# MCU.net
KiCad netlist of a schematic drawn in Altium Designer
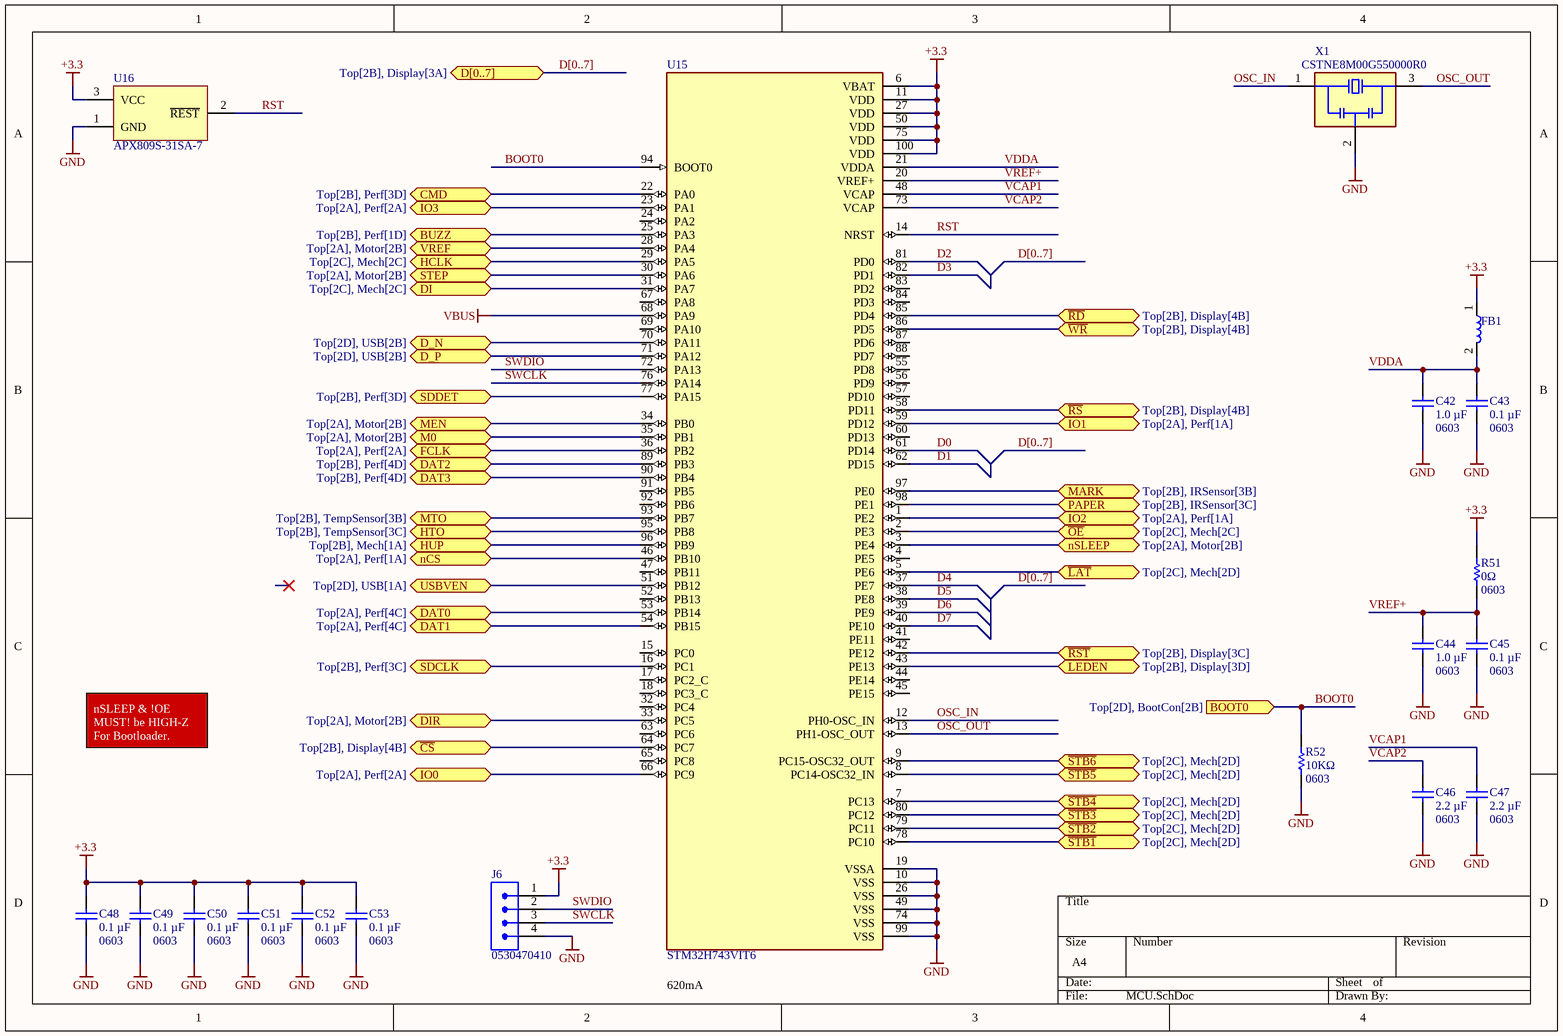
[diagram p0: MCU.SchDoc]

(export (version "E")
  (design (tool "Eeschema 10.0.6"))
  (components
    (comp (ref "C42")
      (value "1.0 µF")
      (footprint "0603")
      (description "1 µF ±10% 50V Ceramic Capacitor X7T 0603 (1608 Metric)")
      (fields (field (name "CASE") "0603") (field (name "TOLERANCE") "±10%") (field (name "VOLTAGE") "50V"))
      (libsource (lib "Murata Electronics") (part "GRM188D71H105KE01J"))
    )
    (comp (ref "C43")
      (value "0.1 µF")
      (footprint "0603")
      (description "0.1 µF ±20% 100V Ceramic Capacitor X7R 0603 (1608 Metric)")
      (fields (field (name "CASE") "0603") (field (name "TOLERANCE") "±20%") (field (name "VOLTAGE") "100V"))
      (libsource (lib "Murata Electronics") (part "GRM188R72A104MA35J"))
    )
    (comp (ref "C44")
      (value "1.0 µF")
      (footprint "0603")
      (description "1 µF ±10% 50V Ceramic Capacitor X7T 0603 (1608 Metric)")
      (fields (field (name "CASE") "0603") (field (name "TOLERANCE") "±10%") (field (name "VOLTAGE") "50V"))
      (libsource (lib "Murata Electronics") (part "GRM188D71H105KE01J"))
    )
    (comp (ref "C45")
      (value "0.1 µF")
      (footprint "0603")
      (description "0.1 µF ±20% 100V Ceramic Capacitor X7R 0603 (1608 Metric)")
      (fields (field (name "CASE") "0603") (field (name "TOLERANCE") "±20%") (field (name "VOLTAGE") "100V"))
      (libsource (lib "Murata Electronics") (part "GRM188R72A104MA35J"))
    )
    (comp (ref "C46")
      (value "2.2 µF")
      (footprint "0603")
      (description "2.2 µF ±10% 25V Ceramic Capacitor X5R 0603 (1608 Metric)")
      (fields (field (name "CASE") "0603") (field (name "TOLERANCE") "±10%") (field (name "VOLTAGE") "25V"))
      (libsource (lib "Murata Electronics") (part "GRM188R61E225KA12J"))
    )
    (comp (ref "C47")
      (value "2.2 µF")
      (footprint "0603")
      (description "2.2 µF ±10% 25V Ceramic Capacitor X5R 0603 (1608 Metric)")
      (fields (field (name "CASE") "0603") (field (name "TOLERANCE") "±10%") (field (name "VOLTAGE") "25V"))
      (libsource (lib "Murata Electronics") (part "GRM188R61E225KA12J"))
    )
    (comp (ref "C48")
      (value "0.1 µF")
      (footprint "0603")
      (description "0.1 µF ±20% 100V Ceramic Capacitor X7R 0603 (1608 Metric)")
      (fields (field (name "CASE") "0603") (field (name "TOLERANCE") "±20%") (field (name "VOLTAGE") "100V"))
      (libsource (lib "Murata Electronics") (part "GRM188R72A104MA35J"))
    )
    (comp (ref "C49")
      (value "0.1 µF")
      (footprint "0603")
      (description "0.1 µF ±20% 100V Ceramic Capacitor X7R 0603 (1608 Metric)")
      (fields (field (name "CASE") "0603") (field (name "TOLERANCE") "±20%") (field (name "VOLTAGE") "100V"))
      (libsource (lib "Murata Electronics") (part "GRM188R72A104MA35J"))
    )
    (comp (ref "C50")
      (value "0.1 µF")
      (footprint "0603")
      (description "0.1 µF ±20% 100V Ceramic Capacitor X7R 0603 (1608 Metric)")
      (fields (field (name "CASE") "0603") (field (name "TOLERANCE") "±20%") (field (name "VOLTAGE") "100V"))
      (libsource (lib "Murata Electronics") (part "GRM188R72A104MA35J"))
    )
    (comp (ref "C51")
      (value "0.1 µF")
      (footprint "0603")
      (description "0.1 µF ±20% 100V Ceramic Capacitor X7R 0603 (1608 Metric)")
      (fields (field (name "CASE") "0603") (field (name "TOLERANCE") "±20%") (field (name "VOLTAGE") "100V"))
      (libsource (lib "Murata Electronics") (part "GRM188R72A104MA35J"))
    )
    (comp (ref "C52")
      (value "0.1 µF")
      (footprint "0603")
      (description "0.1 µF ±20% 100V Ceramic Capacitor X7R 0603 (1608 Metric)")
      (fields (field (name "CASE") "0603") (field (name "TOLERANCE") "±20%") (field (name "VOLTAGE") "100V"))
      (libsource (lib "Murata Electronics") (part "GRM188R72A104MA35J"))
    )
    (comp (ref "C53")
      (value "0.1 µF")
      (footprint "0603")
      (description "0.1 µF ±20% 100V Ceramic Capacitor X7R 0603 (1608 Metric)")
      (fields (field (name "CASE") "0603") (field (name "TOLERANCE") "±20%") (field (name "VOLTAGE") "100V"))
      (libsource (lib "Murata Electronics") (part "GRM188R72A104MA35J"))
    )
    (comp (ref "FB1")
      (value "MPZ1608S221ATA00")
      (footprint "0603")
      (description "220 Ohms @ 100 MHz 1 Power Line Ferrite Bead 0603 (1608 Metric) 2.2A 50mOhm")
      (libsource (lib "TDK Corporation") (part "MPZ1608S221ATA00"))
    )
    (comp (ref "J6")
      (value "0530470410")
      (footprint "4POS")
      (description "Connector Header Through Hole 4 position 0.049\" (1.25mm)")
      (libsource (lib "Molex") (part "0530470410"))
    )
    (comp (ref "R51")
      (value "0Ω")
      (footprint "0603")
      (description "0 Ohms Jumper Chip Resistor 0603 (1608 Metric) Automotive AEC-Q200 Thick Film")
      (fields
        (field (name "CASE") "0603")
        (field (name "TOLERANCE") "0")
        (field (name "Comment") "RMCF0603ZT0R00")
      )
      (libsource (lib "Stackpole Electronics Inc") (part "RMCF0603ZT0R00"))
    )
    (comp (ref "R52")
      (value "10KΩ")
      (footprint "0603")
      (description "10 kOhms ±1% 0.1W, 1/10W Chip Resistor 0603 (1608 Metric) Automotive AEC-Q200 Thick Film")
      (fields (field (name "CASE") "0603") (field (name "TOLERANCE") "1%") (field (name "POWER") "0.1W"))
      (libsource (lib "Stackpole Electronics Inc") (part "RMCF0603FG10K0"))
    )
    (comp (ref "U15")
      (value "STM32H743VIT6")
      (footprint "100-LQFP")
      (libsource (lib "STMicroelectronics") (part "STM32H743VIT6"))
    )
    (comp (ref "U16")
      (value "APX809S-31SA-7")
      (footprint "SOT-23-3")
      (description "Supervisor Push-Pull, Totem Pole 1 Channel SOT-23-3")
      (libsource (lib "Diodes Incorporated") (part "APX809S-31SA-7"))
    )
    (comp (ref "X1")
      (value "CSTNE8M00G550000R0")
      (footprint "3-SMD")
      (description "8 MHz Ceramic Resonator Built in Capacitor 33 pF ±0.2% 40 Ohms -40°C ~ 85°C Surface Mount")
      (libsource (lib "Murata Electronics") (part "CSTNE8M00G550000R0"))
    )
  )
  (nets
    (net (code "1") (name "+3.3") (class "Default")
      (node (ref "C48") (pin "2") (pinfunction "2_2") (pintype "passive"))
      (node (ref "C49") (pin "2") (pinfunction "2_2") (pintype "passive"))
      (node (ref "C50") (pin "2") (pinfunction "2_2") (pintype "passive"))
      (node (ref "C51") (pin "2") (pinfunction "2_2") (pintype "passive"))
      (node (ref "C52") (pin "2") (pinfunction "2_2") (pintype "passive"))
      (node (ref "C53") (pin "2") (pinfunction "2_2") (pintype "passive"))
      (node (ref "FB1") (pin "1") (pinfunction "1_1") (pintype "passive"))
      (node (ref "J6") (pin "1") (pinfunction "1_1") (pintype "passive"))
      (node (ref "R51") (pin "1") (pinfunction "1_1") (pintype "passive"))
      (node (ref "U15") (pin "100") (pinfunction "VDD_100") (pintype "power_in"))
      (node (ref "U15") (pin "11") (pinfunction "VDD_11") (pintype "power_in"))
      (node (ref "U15") (pin "27") (pinfunction "VDD_27") (pintype "power_in"))
      (node (ref "U15") (pin "50") (pinfunction "VDD_50") (pintype "power_in"))
      (node (ref "U15") (pin "6") (pinfunction "VBAT_6") (pintype "power_in"))
      (node (ref "U15") (pin "75") (pinfunction "VDD_75") (pintype "power_in"))
      (node (ref "U16") (pin "3") (pinfunction "VCC_3") (pintype "passive"))
    )
    (net (code "2") (name "/BOOT0") (class "Default")
      (node (ref "R52") (pin "2") (pinfunction "2_2") (pintype "passive"))
      (node (ref "U15") (pin "94") (pinfunction "BOOT0_94") (pintype "input"))
    )
    (net (code "3") (name "/BUZZ") (class "Default")
      (node (ref "U15") (pin "25") (pinfunction "PA3_25") (pintype "bidirectional"))
    )
    (net (code "4") (name "/CMD") (class "Default")
      (node (ref "U15") (pin "22") (pinfunction "PA0_22") (pintype "bidirectional"))
    )
    (net (code "5") (name "/D0") (class "Default")
      (node (ref "U15") (pin "61") (pinfunction "PD14_61") (pintype "bidirectional"))
    )
    (net (code "6") (name "/D1") (class "Default")
      (node (ref "U15") (pin "62") (pinfunction "PD15_62") (pintype "bidirectional"))
    )
    (net (code "7") (name "/D2") (class "Default")
      (node (ref "U15") (pin "81") (pinfunction "PD0_81") (pintype "bidirectional"))
    )
    (net (code "8") (name "/D3") (class "Default")
      (node (ref "U15") (pin "82") (pinfunction "PD1_82") (pintype "bidirectional"))
    )
    (net (code "9") (name "/D4") (class "Default")
      (node (ref "U15") (pin "37") (pinfunction "PE7_37") (pintype "bidirectional"))
    )
    (net (code "10") (name "/D5") (class "Default")
      (node (ref "U15") (pin "38") (pinfunction "PE8_38") (pintype "bidirectional"))
    )
    (net (code "11") (name "/D6") (class "Default")
      (node (ref "U15") (pin "39") (pinfunction "PE9_39") (pintype "bidirectional"))
    )
    (net (code "12") (name "/D7") (class "Default")
      (node (ref "U15") (pin "40") (pinfunction "PE10_40") (pintype "bidirectional"))
    )
    (net (code "13") (name "/DAT0") (class "Default")
      (node (ref "U15") (pin "53") (pinfunction "PB14_53") (pintype "bidirectional"))
    )
    (net (code "14") (name "/DAT1") (class "Default")
      (node (ref "U15") (pin "54") (pinfunction "PB15_54") (pintype "bidirectional"))
    )
    (net (code "15") (name "/DAT2") (class "Default")
      (node (ref "U15") (pin "89") (pinfunction "PB3_89") (pintype "bidirectional"))
    )
    (net (code "16") (name "/DAT3") (class "Default")
      (node (ref "U15") (pin "90") (pinfunction "PB4_90") (pintype "bidirectional"))
    )
    (net (code "17") (name "/DI") (class "Default")
      (node (ref "U15") (pin "31") (pinfunction "PA7_31") (pintype "bidirectional"))
    )
    (net (code "18") (name "/DIR") (class "Default")
      (node (ref "U15") (pin "33") (pinfunction "PC5_33") (pintype "bidirectional"))
    )
    (net (code "20") (name "/D_N") (class "Default")
      (node (ref "U15") (pin "70") (pinfunction "PA11_70") (pintype "bidirectional"))
    )
    (net (code "21") (name "/D_P") (class "Default")
      (node (ref "U15") (pin "71") (pinfunction "PA12_71") (pintype "bidirectional"))
    )
    (net (code "22") (name "/FCLK") (class "Default")
      (node (ref "U15") (pin "36") (pinfunction "PB2_36") (pintype "bidirectional"))
    )
    (net (code "23") (name "/HCLK") (class "Default")
      (node (ref "U15") (pin "29") (pinfunction "PA5_29") (pintype "bidirectional"))
    )
    (net (code "24") (name "/HTO") (class "Default")
      (node (ref "U15") (pin "95") (pinfunction "PB8_95") (pintype "bidirectional"))
    )
    (net (code "25") (name "/HUP") (class "Default")
      (node (ref "U15") (pin "96") (pinfunction "PB9_96") (pintype "bidirectional"))
    )
    (net (code "26") (name "/IO0") (class "Default")
      (node (ref "U15") (pin "66") (pinfunction "PC9_66") (pintype "bidirectional"))
    )
    (net (code "27") (name "/IO1") (class "Default")
      (node (ref "U15") (pin "59") (pinfunction "PD12_59") (pintype "bidirectional"))
    )
    (net (code "28") (name "/IO2") (class "Default")
      (node (ref "U15") (pin "1") (pinfunction "PE2_1") (pintype "bidirectional"))
    )
    (net (code "29") (name "/IO3") (class "Default")
      (node (ref "U15") (pin "23") (pinfunction "PA1_23") (pintype "bidirectional"))
    )
    (net (code "30") (name "/LEDEN") (class "Default")
      (node (ref "U15") (pin "43") (pinfunction "PE13_43") (pintype "bidirectional"))
    )
    (net (code "31") (name "/M0") (class "Default")
      (node (ref "U15") (pin "35") (pinfunction "PB1_35") (pintype "bidirectional"))
    )
    (net (code "32") (name "/MARK") (class "Default")
      (node (ref "U15") (pin "97") (pinfunction "PE0_97") (pintype "bidirectional"))
    )
    (net (code "33") (name "/MEN") (class "Default")
      (node (ref "U15") (pin "34") (pinfunction "PB0_34") (pintype "bidirectional"))
    )
    (net (code "34") (name "/MTO") (class "Default")
      (node (ref "U15") (pin "93") (pinfunction "PB7_93") (pintype "bidirectional"))
    )
    (net (code "35") (name "/OSC_IN") (class "Default")
      (node (ref "U15") (pin "12") (pinfunction "PH0-OSC_IN_12") (pintype "bidirectional"))
      (node (ref "X1") (pin "1") (pinfunction "IN_1") (pintype "passive"))
    )
    (net (code "36") (name "/OSC_OUT") (class "Default")
      (node (ref "U15") (pin "13") (pinfunction "PH1-OSC_OUT_13") (pintype "bidirectional"))
      (node (ref "X1") (pin "3") (pinfunction "OUT_3") (pintype "passive"))
    )
    (net (code "37") (name "/PAPER") (class "Default")
      (node (ref "U15") (pin "98") (pinfunction "PE1_98") (pintype "bidirectional"))
    )
    (net (code "38") (name "/RST") (class "Default")
      (node (ref "U15") (pin "14") (pinfunction "NRST_14") (pintype "bidirectional"))
      (node (ref "U16") (pin "2") (pinfunction "~{REST}_2") (pintype "passive"))
    )
    (net (code "39") (name "/SDCLK") (class "Default")
      (node (ref "U15") (pin "16") (pinfunction "PC1_16") (pintype "bidirectional"))
    )
    (net (code "40") (name "/SDDET") (class "Default")
      (node (ref "U15") (pin "77") (pinfunction "PA15_77") (pintype "bidirectional"))
    )
    (net (code "41") (name "/STEP") (class "Default")
      (node (ref "U15") (pin "30") (pinfunction "PA6_30") (pintype "bidirectional"))
    )
    (net (code "42") (name "/SWCLK") (class "Default")
      (node (ref "J6") (pin "3") (pinfunction "3_3") (pintype "passive"))
      (node (ref "U15") (pin "76") (pinfunction "PA14_76") (pintype "bidirectional"))
    )
    (net (code "43") (name "/SWDIO") (class "Default")
      (node (ref "J6") (pin "2") (pinfunction "2_2") (pintype "passive"))
      (node (ref "U15") (pin "72") (pinfunction "PA13_72") (pintype "bidirectional"))
    )
    (net (code "44") (name "/USBVEN") (class "Default")
      (node (ref "U15") (pin "51") (pinfunction "PB12_51") (pintype "bidirectional"))
    )
    (net (code "45") (name "/VCAP1") (class "Default")
      (node (ref "C47") (pin "2") (pinfunction "2_2") (pintype "passive"))
      (node (ref "U15") (pin "48") (pinfunction "VCAP_48") (pintype "power_in"))
    )
    (net (code "46") (name "/VCAP2") (class "Default")
      (node (ref "C46") (pin "2") (pinfunction "2_2") (pintype "passive"))
      (node (ref "U15") (pin "73") (pinfunction "VCAP_73") (pintype "power_in"))
    )
    (net (code "47") (name "/VDDA") (class "Default")
      (node (ref "C42") (pin "2") (pinfunction "2_2") (pintype "passive"))
      (node (ref "C43") (pin "2") (pinfunction "2_2") (pintype "passive"))
      (node (ref "FB1") (pin "2") (pinfunction "2_2") (pintype "passive"))
      (node (ref "U15") (pin "21") (pinfunction "VDDA_21") (pintype "power_in"))
    )
    (net (code "48") (name "/VREF") (class "Default")
      (node (ref "U15") (pin "28") (pinfunction "PA4_28") (pintype "bidirectional"))
    )
    (net (code "49") (name "/VREF+") (class "Default")
      (node (ref "C44") (pin "2") (pinfunction "2_2") (pintype "passive"))
      (node (ref "C45") (pin "2") (pinfunction "2_2") (pintype "passive"))
      (node (ref "R51") (pin "2") (pinfunction "2_2") (pintype "passive"))
      (node (ref "U15") (pin "20") (pinfunction "VREF+_20") (pintype "power_in"))
    )
    (net (code "50") (name "/nCS") (class "Default")
      (node (ref "U15") (pin "46") (pinfunction "PB10_46") (pintype "bidirectional"))
    )
    (net (code "51") (name "/nSLEEP") (class "Default")
      (node (ref "U15") (pin "3") (pinfunction "PE4_3") (pintype "bidirectional"))
    )
    (net (code "52") (name "/~{CS}") (class "Default")
      (node (ref "U15") (pin "64") (pinfunction "PC7_64") (pintype "bidirectional"))
    )
    (net (code "53") (name "/~{LAT}") (class "Default")
      (node (ref "U15") (pin "5") (pinfunction "PE6_5") (pintype "bidirectional"))
    )
    (net (code "54") (name "/~{OE}") (class "Default")
      (node (ref "U15") (pin "2") (pinfunction "PE3_2") (pintype "bidirectional"))
    )
    (net (code "55") (name "/~{RD}") (class "Default")
      (node (ref "U15") (pin "85") (pinfunction "PD4_85") (pintype "bidirectional"))
    )
    (net (code "56") (name "/~{RST}") (class "Default")
      (node (ref "U15") (pin "42") (pinfunction "PE12_42") (pintype "bidirectional"))
    )
    (net (code "57") (name "/~{RS}") (class "Default")
      (node (ref "U15") (pin "58") (pinfunction "PD11_58") (pintype "bidirectional"))
    )
    (net (code "58") (name "/~{STB1}") (class "Default")
      (node (ref "U15") (pin "78") (pinfunction "PC10_78") (pintype "bidirectional"))
    )
    (net (code "59") (name "/~{STB2}") (class "Default")
      (node (ref "U15") (pin "79") (pinfunction "PC11_79") (pintype "bidirectional"))
    )
    (net (code "60") (name "/~{STB3}") (class "Default")
      (node (ref "U15") (pin "80") (pinfunction "PC12_80") (pintype "bidirectional"))
    )
    (net (code "61") (name "/~{STB4}") (class "Default")
      (node (ref "U15") (pin "7") (pinfunction "PC13_7") (pintype "bidirectional"))
    )
    (net (code "62") (name "/~{STB5}") (class "Default")
      (node (ref "U15") (pin "8") (pinfunction "PC14-OSC32_IN_8") (pintype "bidirectional"))
    )
    (net (code "63") (name "/~{STB6}") (class "Default")
      (node (ref "U15") (pin "9") (pinfunction "PC15-OSC32_OUT_9") (pintype "bidirectional"))
    )
    (net (code "64") (name "/~{WR}") (class "Default")
      (node (ref "U15") (pin "86") (pinfunction "PD5_86") (pintype "bidirectional"))
    )
    (net (code "65") (name "GND") (class "Default")
      (node (ref "C42") (pin "1") (pinfunction "1_1") (pintype "passive"))
      (node (ref "C43") (pin "1") (pinfunction "1_1") (pintype "passive"))
      (node (ref "C44") (pin "1") (pinfunction "1_1") (pintype "passive"))
      (node (ref "C45") (pin "1") (pinfunction "1_1") (pintype "passive"))
      (node (ref "C46") (pin "1") (pinfunction "1_1") (pintype "passive"))
      (node (ref "C47") (pin "1") (pinfunction "1_1") (pintype "passive"))
      (node (ref "C48") (pin "1") (pinfunction "1_1") (pintype "passive"))
      (node (ref "C49") (pin "1") (pinfunction "1_1") (pintype "passive"))
      (node (ref "C50") (pin "1") (pinfunction "1_1") (pintype "passive"))
      (node (ref "C51") (pin "1") (pinfunction "1_1") (pintype "passive"))
      (node (ref "C52") (pin "1") (pinfunction "1_1") (pintype "passive"))
      (node (ref "C53") (pin "1") (pinfunction "1_1") (pintype "passive"))
      (node (ref "J6") (pin "4") (pinfunction "4_4") (pintype "passive"))
      (node (ref "R52") (pin "1") (pinfunction "1_1") (pintype "passive"))
      (node (ref "U15") (pin "10") (pinfunction "VSS_10") (pintype "power_in"))
      (node (ref "U15") (pin "19") (pinfunction "VSSA_19") (pintype "power_in"))
      (node (ref "U15") (pin "26") (pinfunction "VSS_26") (pintype "power_in"))
      (node (ref "U15") (pin "49") (pinfunction "VSS_49") (pintype "power_in"))
      (node (ref "U15") (pin "74") (pinfunction "VSS_74") (pintype "power_in"))
      (node (ref "U15") (pin "99") (pinfunction "VSS_99") (pintype "power_in"))
      (node (ref "U16") (pin "1") (pinfunction "GND_1") (pintype "passive"))
      (node (ref "X1") (pin "2") (pinfunction "GND_2") (pintype "power_in"))
    )
    (net (code "66") (name "VBUS") (class "Default")
      (node (ref "U15") (pin "68") (pinfunction "PA9_68") (pintype "bidirectional"))
    )
    (net (code "67") (name "unconnected-(U15-PA2-Pad24)") (class "Default")
      (node (ref "U15") (pin "24") (pinfunction "PA2_24") (pintype "bidirectional"))
    )
    (net (code "68") (name "unconnected-(U15-PA8-Pad67)") (class "Default")
      (node (ref "U15") (pin "67") (pinfunction "PA8_67") (pintype "bidirectional"))
    )
    (net (code "69") (name "unconnected-(U15-PA10-Pad69)") (class "Default")
      (node (ref "U15") (pin "69") (pinfunction "PA10_69") (pintype "bidirectional"))
    )
    (net (code "70") (name "unconnected-(U15-PB5-Pad91)") (class "Default")
      (node (ref "U15") (pin "91") (pinfunction "PB5_91") (pintype "bidirectional"))
    )
    (net (code "71") (name "unconnected-(U15-PB6-Pad92)") (class "Default")
      (node (ref "U15") (pin "92") (pinfunction "PB6_92") (pintype "bidirectional"))
    )
    (net (code "72") (name "unconnected-(U15-PB11-Pad47)") (class "Default")
      (node (ref "U15") (pin "47") (pinfunction "PB11_47") (pintype "bidirectional"))
    )
    (net (code "73") (name "unconnected-(U15-PB13-Pad52)") (class "Default")
      (node (ref "U15") (pin "52") (pinfunction "PB13_52") (pintype "bidirectional"))
    )
    (net (code "74") (name "unconnected-(U15-PC0-Pad15)") (class "Default")
      (node (ref "U15") (pin "15") (pinfunction "PC0_15") (pintype "bidirectional"))
    )
    (net (code "75") (name "unconnected-(U15-PC2_C-Pad17)") (class "Default")
      (node (ref "U15") (pin "17") (pinfunction "PC2_C_17") (pintype "bidirectional"))
    )
    (net (code "76") (name "unconnected-(U15-PC3_C-Pad18)") (class "Default")
      (node (ref "U15") (pin "18") (pinfunction "PC3_C_18") (pintype "bidirectional"))
    )
    (net (code "77") (name "unconnected-(U15-PC4-Pad32)") (class "Default")
      (node (ref "U15") (pin "32") (pinfunction "PC4_32") (pintype "bidirectional"))
    )
    (net (code "78") (name "unconnected-(U15-PC6-Pad63)") (class "Default")
      (node (ref "U15") (pin "63") (pinfunction "PC6_63") (pintype "bidirectional"))
    )
    (net (code "79") (name "unconnected-(U15-PC8-Pad65)") (class "Default")
      (node (ref "U15") (pin "65") (pinfunction "PC8_65") (pintype "bidirectional"))
    )
    (net (code "80") (name "unconnected-(U15-PD2-Pad83)") (class "Default")
      (node (ref "U15") (pin "83") (pinfunction "PD2_83") (pintype "bidirectional"))
    )
    (net (code "81") (name "unconnected-(U15-PD3-Pad84)") (class "Default")
      (node (ref "U15") (pin "84") (pinfunction "PD3_84") (pintype "bidirectional"))
    )
    (net (code "82") (name "unconnected-(U15-PD6-Pad87)") (class "Default")
      (node (ref "U15") (pin "87") (pinfunction "PD6_87") (pintype "bidirectional"))
    )
    (net (code "83") (name "unconnected-(U15-PD7-Pad88)") (class "Default")
      (node (ref "U15") (pin "88") (pinfunction "PD7_88") (pintype "bidirectional"))
    )
    (net (code "84") (name "unconnected-(U15-PD8-Pad55)") (class "Default")
      (node (ref "U15") (pin "55") (pinfunction "PD8_55") (pintype "bidirectional"))
    )
    (net (code "85") (name "unconnected-(U15-PD9-Pad56)") (class "Default")
      (node (ref "U15") (pin "56") (pinfunction "PD9_56") (pintype "bidirectional"))
    )
    (net (code "86") (name "unconnected-(U15-PD10-Pad57)") (class "Default")
      (node (ref "U15") (pin "57") (pinfunction "PD10_57") (pintype "bidirectional"))
    )
    (net (code "87") (name "unconnected-(U15-PD13-Pad60)") (class "Default")
      (node (ref "U15") (pin "60") (pinfunction "PD13_60") (pintype "bidirectional"))
    )
    (net (code "88") (name "unconnected-(U15-PE5-Pad4)") (class "Default")
      (node (ref "U15") (pin "4") (pinfunction "PE5_4") (pintype "bidirectional"))
    )
    (net (code "89") (name "unconnected-(U15-PE11-Pad41)") (class "Default")
      (node (ref "U15") (pin "41") (pinfunction "PE11_41") (pintype "bidirectional"))
    )
    (net (code "90") (name "unconnected-(U15-PE14-Pad44)") (class "Default")
      (node (ref "U15") (pin "44") (pinfunction "PE14_44") (pintype "bidirectional"))
    )
    (net (code "91") (name "unconnected-(U15-PE15-Pad45)") (class "Default")
      (node (ref "U15") (pin "45") (pinfunction "PE15_45") (pintype "bidirectional"))
    )
  )
)
